# Duubel_v3.net
KiCad netlist of a schematic drawn in Altium Designer
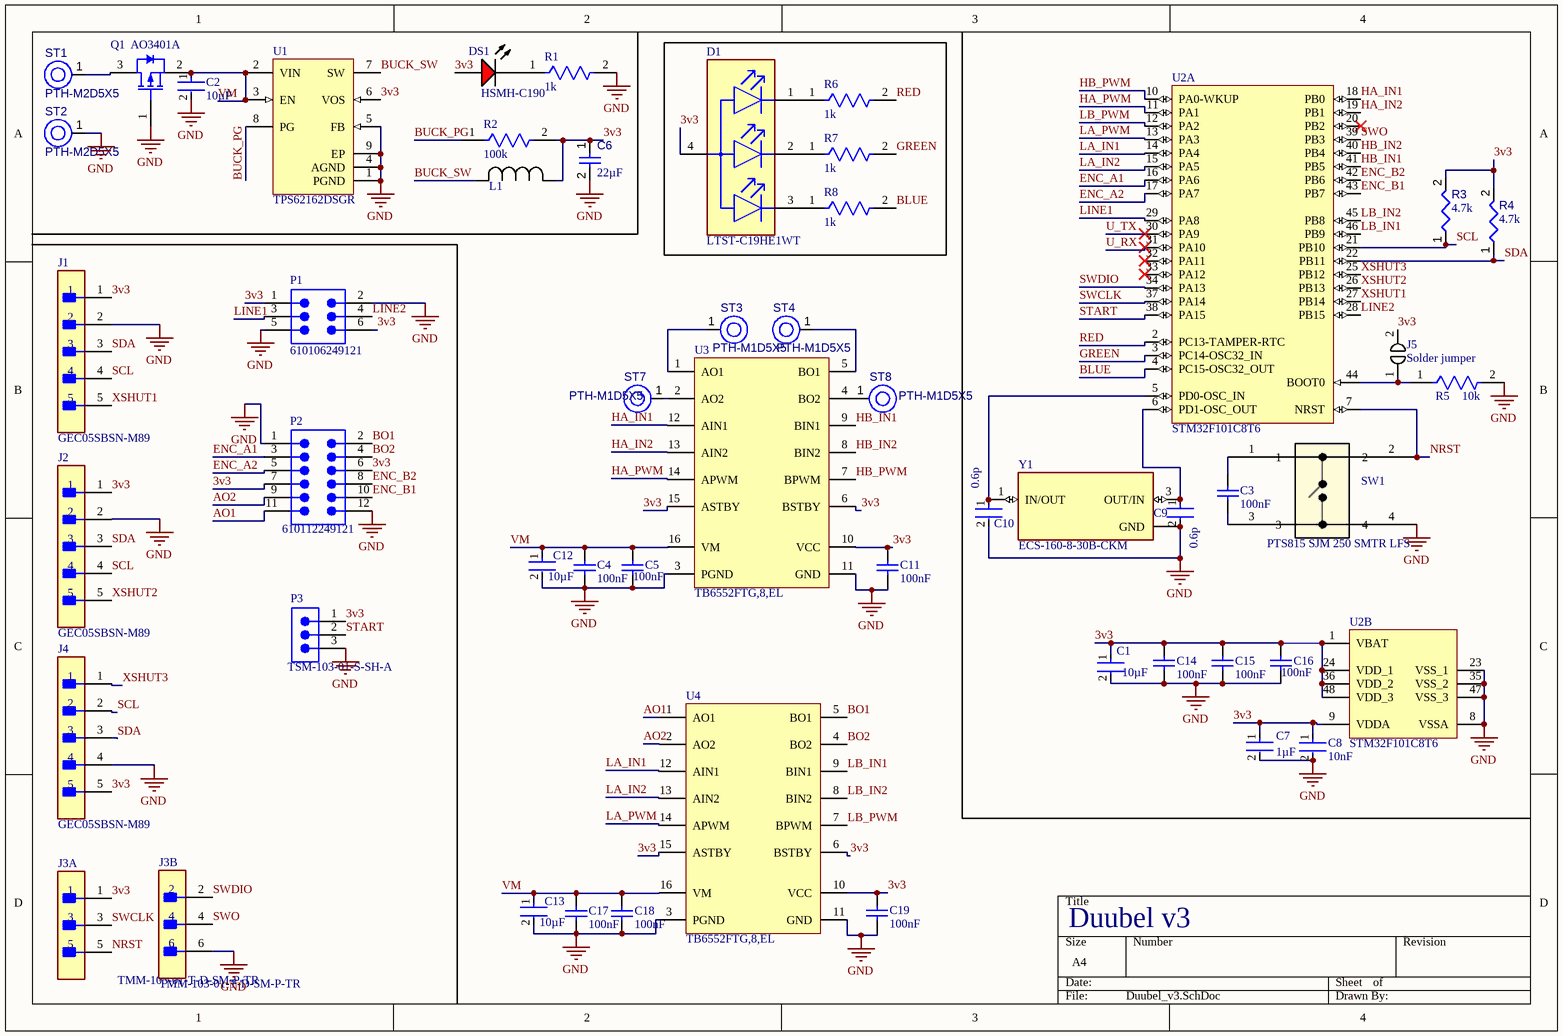
[diagram p0: Duubel_v3.SchDoc]

(export (version "E")
  (design (tool "Eeschema 10.0.6"))
  (components
    (comp (ref "C1")
      (value "10µF")
      (footprint "FP-CL10-IPC_B")
      (fields (field (name "Comment") "CL10A106KP8NNND"))
      (libsource (lib "TalTech") (part "b4654b650e69147ec39a6b967a45e02"))
    )
    (comp (ref "C2")
      (value "10µF")
      (footprint "FP-CL10-IPC_B")
      (fields (field (name "Comment") "CL10A106KP8NNND"))
      (libsource (lib "TalTech") (part "b4654b650e69147ec39a6b967a45e02"))
    )
    (comp (ref "C3")
      (value "100nF")
      (footprint "CAPC1608X90X35LL15T15")
      (fields (field (name "Comment") "0603YC104MAT4A"))
      (libsource (lib "TalTech") (part "CAP"))
    )
    (comp (ref "C4")
      (value "100nF")
      (footprint "CAPC1608X90X35LL15T15")
      (fields (field (name "Comment") "0603YC104MAT4A"))
      (libsource (lib "TalTech") (part "CAP"))
    )
    (comp (ref "C5")
      (value "100nF")
      (footprint "CAPC1608X90X35LL15T15")
      (fields (field (name "Comment") "0603YC104MAT4A"))
      (libsource (lib "TalTech") (part "CAP"))
    )
    (comp (ref "C6")
      (value "22µF")
      (footprint "CAPC0805(2012)145_L")
      (description "Chip Capacitor, 22µF +/-40%, 16V, 0805, Thickness 1.45 mm")
      (fields (field (name "TOLERANCE") "5%") (field (name "Comment") "Capacitor 22µF +/-40% 16V 0805"))
      (libsource (lib "TalTech") (part "CAP-NP-2"))
    )
    (comp (ref "C7")
      (value "1µF")
      (footprint "FP-0805-L_2_01_0_2-W_1_25-IPC_B")
      (fields (field (name "Comment") "08053C105K4Z2A"))
      (libsource (lib "TalTech") (part "b4654b650e69147ec39a6b967a45e02"))
    )
    (comp (ref "C8")
      (value "10nF")
      (footprint "FP-CL10-IPC_B")
      (fields (field (name "Comment") "CL10B103KB8NFNC"))
      (libsource (lib "TalTech") (part "b4654b650e69147ec39a6b967a45e02"))
    )
    (comp (ref "C9")
      (value "0.6p")
      (footprint "FP-CGA3E-0_3-0_1-MFG")
      (description "Cap Ceramic 6pF 50V C0G 0.5pF Pad SMD 0603 +125°C Automotive T/R")
      (libsource (lib "Altium Content Vault") (part "b4654b650e69147ec39a6b967a45e02"))
    )
    (comp (ref "C10")
      (value "0.6p")
      (footprint "FP-CGA3E-0_3-0_1-MFG")
      (description "Cap Ceramic 6pF 50V C0G 0.5pF Pad SMD 0603 +125°C Automotive T/R")
      (libsource (lib "Altium Content Vault") (part "b4654b650e69147ec39a6b967a45e02"))
    )
    (comp (ref "C11")
      (value "100nF")
      (footprint "CAPC1608X90X35LL15T15")
      (fields (field (name "Comment") "0603YC104MAT4A"))
      (libsource (lib "TalTech") (part "CAP"))
    )
    (comp (ref "C12")
      (value "10µF")
      (footprint "FP-CL10-IPC_B")
      (fields (field (name "Comment") "CL10A106KP8NNND"))
      (libsource (lib "TalTech") (part "b4654b650e69147ec39a6b967a45e02"))
    )
    (comp (ref "C13")
      (value "10µF")
      (footprint "FP-CL10-IPC_B")
      (fields (field (name "Comment") "CL10A106KP8NNND"))
      (libsource (lib "TalTech") (part "b4654b650e69147ec39a6b967a45e02"))
    )
    (comp (ref "C14")
      (value "100nF")
      (footprint "CAPC1608X90X35LL15T15")
      (fields (field (name "Comment") "0603YC104MAT4A"))
      (libsource (lib "TalTech") (part "CAP"))
    )
    (comp (ref "C15")
      (value "100nF")
      (footprint "CAPC1608X90X35LL15T15")
      (fields (field (name "Comment") "0603YC104MAT4A"))
      (libsource (lib "TalTech") (part "CAP"))
    )
    (comp (ref "C16")
      (value "100nF")
      (footprint "CAPC1608X90X35LL15T15")
      (fields (field (name "Comment") "0603YC104MAT4A"))
      (libsource (lib "TalTech") (part "CAP"))
    )
    (comp (ref "C17")
      (value "100nF")
      (footprint "CAPC1608X90X35LL15T15")
      (fields (field (name "Comment") "0603YC104MAT4A"))
      (libsource (lib "TalTech") (part "CAP"))
    )
    (comp (ref "C18")
      (value "100nF")
      (footprint "CAPC1608X90X35LL15T15")
      (fields (field (name "Comment") "0603YC104MAT4A"))
      (libsource (lib "TalTech") (part "CAP"))
    )
    (comp (ref "C19")
      (value "100nF")
      (footprint "CAPC1608X90X35LL15T15")
      (fields (field (name "Comment") "0603YC104MAT4A"))
      (libsource (lib "TalTech") (part "CAP"))
    )
    (comp (ref "D1")
      (value "LTST-C19HE1WT")
      (footprint "FP-LTST-C19HE1WT-MFG")
      (description "Single Color LED, White Diffused")
      (libsource (lib "TalTech") (part "2c4e1fdd461916b293eda504ca5a2b6"))
    )
    (comp (ref "DS1")
      (value "HSMH-C190")
      (footprint "AVAG-HSMX-C190_V")
      (description "LED Uni-Color Red, 65 mW, 20 mA, -40 to 85 degC, 2-Pin SMD, RoHS, Tape and Reel")
      (fields (field (name "POWER") "78mW") (field (name "MANUFACTURER") "Avago"))
      (libsource (lib "TalTech") (part "LED-RED-AK-2"))
    )
    (comp (ref "J1")
      (value "GEC05SBSN-M89")
      (footprint "FP-GEC05SBSN-M89-MFG")
      (description "Board Connector, 5 Contact(s), 1 Row(s), Male, Right Angle, Surface Mount Terminal")
      (libsource (lib "TalTech") (part "051ac7c1f60a91215dd69c4e70fad1a"))
    )
    (comp (ref "J2")
      (value "GEC05SBSN-M89")
      (footprint "FP-GEC05SBSN-M89-MFG")
      (description "Board Connector, 5 Contact(s), 1 Row(s), Male, Right Angle, Surface Mount Terminal")
      (libsource (lib "TalTech") (part "051ac7c1f60a91215dd69c4e70fad1a"))
    )
    (comp (ref "J3")
      (value "TMM-103-01-T-D-SM-P-TR")
      (footprint "FP-TMM-103-01-T-D-SM-P-TR-MFG")
      (libsource (lib "TalTech") (part "2654a11fb13586ecb194516b1c997bc"))
    )
    (comp (ref "J4")
      (value "GEC05SBSN-M89")
      (footprint "FP-GEC05SBSN-M89-MFG")
      (description "Board Connector, 5 Contact(s), 1 Row(s), Male, Right Angle, Surface Mount Terminal")
      (libsource (lib "TalTech") (part "051ac7c1f60a91215dd69c4e70fad1a"))
    )
    (comp (ref "J5")
      (value "Solder jumper")
      (footprint "Solder jumper-Footprint-1")
      (libsource (lib "TalTech") (part "New symbol 1"))
    )
    (comp (ref "L1")
      (value "IHHP0805ZHER2R2M01")
      (footprint "IND_IHHP-0805ZH-01_VIS")
      (description "Power Inductor, 2.2UH, Shielded, 1.8A Rohs Compliant: Yes")
      (libsource (lib "TalTech") (part "IHHP0805ZHER2R2M01"))
    )
    (comp (ref "P1")
      (value "610106249121")
      (footprint "610106249121")
      (description "Board Connector, 6 Contact(s), 2 Row(s), Male, Right Angle, Surface Mount Terminal")
      (libsource (lib "TalTech") (part "Header_Male_2R_06P"))
    )
    (comp (ref "P2")
      (value "610112249121")
      (footprint "610112249121")
      (description "Board Connector, 12 Contact(s), 2 Row(s), Male, Right Angle, Surface Mount Terminal")
      (libsource (lib "TalTech") (part "Header_Male_2R_12P"))
    )
    (comp (ref "P3")
      (value "TSM-103-01-S-SH-A")
      (footprint "SMTC-TSM-103-01-X-SH-A")
      (libsource (lib "TalTech") (part "SMTC-TSM-103-01-X-SH-A"))
    )
    (comp (ref "Q1")
      (value "AO3401A")
      (footprint "AO-SOT-23-3L_V")
      (libsource (lib "TalTech") (part "PEMOS-GSD-3"))
    )
    (comp (ref "R1")
      (value "1k")
      (footprint "FP-RCA0603-e3-IPC_B")
      (fields
        (field (name "TOLERANCE") "1%")
        (field (name "POWER") "100mW")
        (field (name "Comment") "RCA06031K00FKEA")
      )
      (libsource (lib "TalTech") (part "1029c3af85768c4190bb7ad29bc67b5"))
    )
    (comp (ref "R2")
      (value "100k")
      (footprint "FP-CRCW0603-HPe3-MFG")
      (fields
        (field (name "POWER") "250mW")
        (field (name "TOLERANCE") "5%")
        (field (name "Comment") "CRCW0603100KJNEAHP")
      )
      (libsource (lib "TalTech") (part "1029c3af85768c4190bb7ad29bc67b5"))
    )
    (comp (ref "R3")
      (value "4.7k")
      (footprint "RESC1608X55X25ML10T15")
      (description "Chip Resistor, 4.7 KOhm, +/- 1%, 0.1 W, -55 to 155 degC, 0603 (1608 Metric)")
      (fields (field (name "TOLERANCE") "1%") (field (name "POWER") "100mW"))
      (libsource (lib "TalTech") (part "RES-2"))
    )
    (comp (ref "R4")
      (value "4.7k")
      (footprint "RESC1608X55X25ML10T15")
      (description "Chip Resistor, 4.7 KOhm, +/- 1%, 0.1 W, -55 to 155 degC, 0603 (1608 Metric)")
      (fields (field (name "TOLERANCE") "1%") (field (name "POWER") "100mW"))
      (libsource (lib "TalTech") (part "RES-2"))
    )
    (comp (ref "R5")
      (value "10k")
      (footprint "FP-MCT0603-IPC_A")
      (description "Fixed Resistor, Thin Film, 0.1W, 10000ohm, 75V, 0.1% +/-Tol, 15ppm/Cel, Surface Mount, 0603")
      (fields (field (name "TOLERANCE") "0.1%") (field (name "POWER") "100mW"))
      (libsource (lib "TalTech") (part "1029c3af85768c4190bb7ad29bc67b5"))
    )
    (comp (ref "R6")
      (value "1k")
      (footprint "FP-RCA0603-e3-IPC_B")
      (fields
        (field (name "TOLERANCE") "1%")
        (field (name "POWER") "100mW")
        (field (name "Comment") "RCA06031K00FKEA")
      )
      (libsource (lib "TalTech") (part "1029c3af85768c4190bb7ad29bc67b5"))
    )
    (comp (ref "R7")
      (value "1k")
      (footprint "FP-RCA0603-e3-IPC_B")
      (fields
        (field (name "TOLERANCE") "1%")
        (field (name "POWER") "100mW")
        (field (name "Comment") "RCA06031K00FKEA")
      )
      (libsource (lib "TalTech") (part "1029c3af85768c4190bb7ad29bc67b5"))
    )
    (comp (ref "R8")
      (value "1k")
      (footprint "FP-RCA0603-e3-IPC_B")
      (fields
        (field (name "TOLERANCE") "1%")
        (field (name "POWER") "100mW")
        (field (name "Comment") "RCA06031K00FKEA")
      )
      (libsource (lib "TalTech") (part "1029c3af85768c4190bb7ad29bc67b5"))
    )
    (comp (ref "ST1")
      (value "PTH-M2D5X5")
      (footprint "PTH-M2D5X5")
      (description "M2 PTH (2.5mm), 5mm pad")
      (libsource (lib "TalTech") (part "CMP-00028-00000-1"))
    )
    (comp (ref "ST2")
      (value "PTH-M2D5X5")
      (footprint "PTH-M2D5X5")
      (description "M2 PTH (2.5mm), 5mm pad")
      (libsource (lib "TalTech") (part "CMP-00028-00000-1"))
    )
    (comp (ref "ST3")
      (value "PTH-M1D5X5")
      (footprint "PTH-M2D5X5")
      (description "M1 PTH (2.5mm), 5mm pad")
      (libsource (lib "TalTech") (part "CMP-00028-00000-1"))
    )
    (comp (ref "ST4")
      (value "PTH-M1D5X5")
      (footprint "PTH-M2D5X5")
      (description "M1 PTH (2.5mm), 5mm pad")
      (libsource (lib "TalTech") (part "CMP-00028-00000-1"))
    )
    (comp (ref "ST7")
      (value "PTH-M1D5X5")
      (footprint "PTH-M2D5X5")
      (description "M1 PTH (2.5mm), 5mm pad")
      (libsource (lib "TalTech") (part "CMP-00028-00000-1"))
    )
    (comp (ref "ST8")
      (value "PTH-M1D5X5")
      (footprint "PTH-M2D5X5")
      (description "M1 PTH (2.5mm), 5mm pad")
      (libsource (lib "TalTech") (part "CMP-00028-00000-1"))
    )
    (comp (ref "SW1")
      (value "PTS815 SJM 250 SMTR LFS")
      (footprint "SW4_PTS815 SJM 250 SMTR LFS_CNK")
      (description "No Description Available")
      (libsource (lib "PTS815SJM250SMTRLFS") (part "PTS815 SJM 250 SMTR LFS"))
    )
    (comp (ref "U1")
      (value "TPS62162DSGR")
      (footprint "DSG0008A_V")
      (description "Switching Regulator, Current-mode, 1A, 2250kHz Switching Freq-Max, PDSO8")
      (libsource (lib "TalTech") (part "TI-TPS62162DSG8-1600X900TP"))
    )
    (comp (ref "U2")
      (value "STM32F101C8T6")
      (footprint "STM-LQFP48_N")
      (description "RISC Microcontroller, 32-Bit, FLASH, CORTEX-M3 CPU, 36MHz, CMOS, PQFP48")
      (libsource (lib "TalTech") (part "MC-ARM-STM32F101X8_B-SQ48"))
    )
    (comp (ref "U3")
      (value "TB6552FTG,8,EL")
      (footprint "QFN50P300X300X75_HS-17N")
      (description "Dual-bridge Driver IC For DC Motors")
      (libsource (lib "TalTech") (part "TB6552FTG,8,EL-Symbol-1"))
    )
    (comp (ref "U4")
      (value "TB6552FTG,8,EL")
      (footprint "QFN50P300X300X75_HS-17N")
      (description "Dual-bridge Driver IC For DC Motors")
      (libsource (lib "TalTech") (part "TB6552FTG,8,EL-Symbol-1"))
    )
    (comp (ref "Y1")
      (value "ECS-160-8-30B-CKM")
      (footprint "XTAL_ECS-160-8-30B-CKM")
      (fields (field (name "MF") "{'manufacturer': u'ECS Inc.'}"))
      (libsource (lib "ECS-160-8-30B-CKM") (part "ECS-160-8-30B-CKM"))
    )
  )
  (nets
    (net (code "1") (name "/3v3") (class "Default")
      (node (ref "C1") (pin "1") (pinfunction "1_1") (pintype "passive"))
      (node (ref "C11") (pin "2") (pinfunction "2_2") (pintype "passive"))
      (node (ref "C14") (pin "2") (pinfunction "2_2") (pintype "passive"))
      (node (ref "C15") (pin "2") (pinfunction "2_2") (pintype "passive"))
      (node (ref "C16") (pin "2") (pinfunction "2_2") (pintype "passive"))
      (node (ref "C19") (pin "2") (pinfunction "2_2") (pintype "passive"))
      (node (ref "C6") (pin "1") (pinfunction "1_1") (pintype "passive"))
      (node (ref "C7") (pin "1") (pinfunction "1_1") (pintype "passive"))
      (node (ref "C8") (pin "1") (pinfunction "1_1") (pintype "passive"))
      (node (ref "D1") (pin "4") (pinfunction "A_4") (pintype "passive"))
      (node (ref "DS1") (pin "1") (pinfunction "A_1") (pintype "passive"))
      (node (ref "J1") (pin "1") (pinfunction "1_1") (pintype "passive"))
      (node (ref "J2") (pin "1") (pinfunction "1_1") (pintype "passive"))
      (node (ref "J3") (pin "1") (pinfunction "1_1") (pintype "passive"))
      (node (ref "J4") (pin "5") (pinfunction "5_5") (pintype "passive"))
      (node (ref "J5") (pin "2") (pintype "passive"))
      (node (ref "L1") (pin "1") (pinfunction "1_1") (pintype "passive"))
      (node (ref "P1") (pin "1") (pinfunction "1_1") (pintype "passive"))
      (node (ref "P1") (pin "6") (pinfunction "6_6") (pintype "passive"))
      (node (ref "P2") (pin "6") (pinfunction "6_6") (pintype "passive"))
      (node (ref "P2") (pin "7") (pinfunction "7_7") (pintype "passive"))
      (node (ref "P3") (pin "1") (pinfunction "1_1") (pintype "passive"))
      (node (ref "R2") (pin "2") (pinfunction "2_2") (pintype "passive"))
      (node (ref "R3") (pin "2") (pinfunction "2_2") (pintype "passive"))
      (node (ref "R4") (pin "2") (pinfunction "2_2") (pintype "passive"))
      (node (ref "U1") (pin "6") (pinfunction "VOS_6") (pintype "input"))
      (node (ref "U2") (pin "1") (pinfunction "VBAT_1") (pintype "power_in"))
      (node (ref "U2") (pin "24") (pinfunction "VDD_1_24") (pintype "power_in"))
      (node (ref "U2") (pin "36") (pinfunction "VDD_2_36") (pintype "power_in"))
      (node (ref "U2") (pin "48") (pinfunction "VDD_3_48") (pintype "power_in"))
      (node (ref "U2") (pin "9") (pinfunction "VDDA_9") (pintype "power_in"))
      (node (ref "U3") (pin "10") (pinfunction "VCC_10") (pintype "passive"))
      (node (ref "U3") (pin "15") (pinfunction "ASTBY_15") (pintype "passive"))
      (node (ref "U3") (pin "6") (pinfunction "BSTBY_6") (pintype "passive"))
      (node (ref "U4") (pin "10") (pinfunction "VCC_10") (pintype "passive"))
      (node (ref "U4") (pin "15") (pinfunction "ASTBY_15") (pintype "passive"))
      (node (ref "U4") (pin "6") (pinfunction "BSTBY_6") (pintype "passive"))
    )
    (net (code "2") (name "/AO1") (class "Default")
      (node (ref "P2") (pin "11") (pinfunction "11_11") (pintype "passive"))
      (node (ref "U4") (pin "1") (pinfunction "AO1_1") (pintype "passive"))
    )
    (net (code "3") (name "/AO2") (class "Default")
      (node (ref "P2") (pin "9") (pinfunction "9_9") (pintype "passive"))
      (node (ref "U4") (pin "2") (pinfunction "AO2_2") (pintype "passive"))
    )
    (net (code "4") (name "/BLUE") (class "Default")
      (node (ref "R8") (pin "2") (pinfunction "2_2") (pintype "passive"))
      (node (ref "U2") (pin "4") (pinfunction "PC15-OSC32_OUT_4") (pintype "bidirectional"))
    )
    (net (code "5") (name "/BO1") (class "Default")
      (node (ref "P2") (pin "2") (pinfunction "2_2") (pintype "passive"))
      (node (ref "U4") (pin "5") (pinfunction "BO1_5") (pintype "passive"))
    )
    (net (code "6") (name "/BO2") (class "Default")
      (node (ref "P2") (pin "4") (pinfunction "4_4") (pintype "passive"))
      (node (ref "U4") (pin "4") (pinfunction "BO2_4") (pintype "passive"))
    )
    (net (code "7") (name "/BUCK_PG") (class "Default")
      (node (ref "R2") (pin "1") (pinfunction "1_1") (pintype "passive"))
      (node (ref "U1") (pin "8") (pinfunction "PG_8") (pintype "tri_state"))
    )
    (net (code "8") (name "/BUCK_SW") (class "Default")
      (node (ref "L1") (pin "2") (pinfunction "2_2") (pintype "passive"))
      (node (ref "U1") (pin "7") (pinfunction "SW_7") (pintype "power_in"))
    )
    (net (code "9") (name "/ENC_A1") (class "Default")
      (node (ref "P2") (pin "3") (pinfunction "3_3") (pintype "passive"))
      (node (ref "U2") (pin "16") (pinfunction "PA6_16") (pintype "bidirectional"))
    )
    (net (code "10") (name "/ENC_A2") (class "Default")
      (node (ref "P2") (pin "5") (pinfunction "5_5") (pintype "passive"))
      (node (ref "U2") (pin "17") (pinfunction "PA7_17") (pintype "bidirectional"))
    )
    (net (code "11") (name "/ENC_B1") (class "Default")
      (node (ref "P2") (pin "10") (pinfunction "10_10") (pintype "passive"))
      (node (ref "U2") (pin "43") (pinfunction "PB7_43") (pintype "bidirectional"))
    )
    (net (code "12") (name "/ENC_B2") (class "Default")
      (node (ref "P2") (pin "8") (pinfunction "8_8") (pintype "passive"))
      (node (ref "U2") (pin "42") (pinfunction "PB6_42") (pintype "bidirectional"))
    )
    (net (code "13") (name "/GREEN") (class "Default")
      (node (ref "R7") (pin "2") (pinfunction "2_2") (pintype "passive"))
      (node (ref "U2") (pin "3") (pinfunction "PC14-OSC32_IN_3") (pintype "bidirectional"))
    )
    (net (code "14") (name "/HA_IN1") (class "Default")
      (node (ref "U2") (pin "18") (pinfunction "PB0_18") (pintype "bidirectional"))
      (node (ref "U3") (pin "12") (pinfunction "AIN1_12") (pintype "passive"))
    )
    (net (code "15") (name "/HA_IN2") (class "Default")
      (node (ref "U2") (pin "19") (pinfunction "PB1_19") (pintype "bidirectional"))
      (node (ref "U3") (pin "13") (pinfunction "AIN2_13") (pintype "passive"))
    )
    (net (code "16") (name "/HA_PWM") (class "Default")
      (node (ref "U2") (pin "11") (pinfunction "PA1_11") (pintype "bidirectional"))
      (node (ref "U3") (pin "14") (pinfunction "APWM_14") (pintype "passive"))
    )
    (net (code "17") (name "/HB_IN1") (class "Default")
      (node (ref "U2") (pin "41") (pinfunction "PB5_41") (pintype "bidirectional"))
      (node (ref "U3") (pin "9") (pinfunction "BIN1_9") (pintype "passive"))
    )
    (net (code "18") (name "/HB_IN2") (class "Default")
      (node (ref "U2") (pin "40") (pinfunction "PB4_40") (pintype "bidirectional"))
      (node (ref "U3") (pin "8") (pinfunction "BIN2_8") (pintype "passive"))
    )
    (net (code "19") (name "/HB_PWM") (class "Default")
      (node (ref "U2") (pin "10") (pinfunction "PA0-WKUP_10") (pintype "bidirectional"))
      (node (ref "U3") (pin "7") (pinfunction "BPWM_7") (pintype "passive"))
    )
    (net (code "20") (name "/LA_IN1") (class "Default")
      (node (ref "U2") (pin "14") (pinfunction "PA4_14") (pintype "bidirectional"))
      (node (ref "U4") (pin "12") (pinfunction "AIN1_12") (pintype "passive"))
    )
    (net (code "21") (name "/LA_IN2") (class "Default")
      (node (ref "U2") (pin "15") (pinfunction "PA5_15") (pintype "bidirectional"))
      (node (ref "U4") (pin "13") (pinfunction "AIN2_13") (pintype "passive"))
    )
    (net (code "22") (name "/LA_PWM") (class "Default")
      (node (ref "U2") (pin "13") (pinfunction "PA3_13") (pintype "bidirectional"))
      (node (ref "U4") (pin "14") (pinfunction "APWM_14") (pintype "passive"))
    )
    (net (code "23") (name "/LB_IN1") (class "Default")
      (node (ref "U2") (pin "46") (pinfunction "PB9_46") (pintype "bidirectional"))
      (node (ref "U4") (pin "9") (pinfunction "BIN1_9") (pintype "passive"))
    )
    (net (code "24") (name "/LB_IN2") (class "Default")
      (node (ref "U2") (pin "45") (pinfunction "PB8_45") (pintype "bidirectional"))
      (node (ref "U4") (pin "8") (pinfunction "BIN2_8") (pintype "passive"))
    )
    (net (code "25") (name "/LB_PWM") (class "Default")
      (node (ref "U2") (pin "12") (pinfunction "PA2_12") (pintype "bidirectional"))
      (node (ref "U4") (pin "7") (pinfunction "BPWM_7") (pintype "passive"))
    )
    (net (code "26") (name "/LINE1") (class "Default")
      (node (ref "P1") (pin "3") (pinfunction "3_3") (pintype "passive"))
      (node (ref "U2") (pin "29") (pinfunction "PA8_29") (pintype "bidirectional"))
    )
    (net (code "27") (name "/LINE2") (class "Default")
      (node (ref "P1") (pin "4") (pinfunction "4_4") (pintype "passive"))
      (node (ref "U2") (pin "28") (pinfunction "PB15_28") (pintype "bidirectional"))
    )
    (net (code "28") (name "/NRST") (class "Default")
      (node (ref "J3") (pin "5") (pinfunction "5_5") (pintype "passive"))
      (node (ref "SW1") (pin "2") (pinfunction "2_2") (pintype "passive"))
      (node (ref "U2") (pin "7") (pinfunction "NRST_7") (pintype "bidirectional"))
    )
    (net (code "29") (name "/RED") (class "Default")
      (node (ref "R6") (pin "2") (pinfunction "2_2") (pintype "passive"))
      (node (ref "U2") (pin "2") (pinfunction "PC13-TAMPER-RTC_2") (pintype "bidirectional"))
    )
    (net (code "30") (name "/SCL") (class "Default")
      (node (ref "J1") (pin "4") (pinfunction "4_4") (pintype "passive"))
      (node (ref "J2") (pin "4") (pinfunction "4_4") (pintype "passive"))
      (node (ref "J4") (pin "2") (pinfunction "2_2") (pintype "passive"))
      (node (ref "R3") (pin "1") (pinfunction "1_1") (pintype "passive"))
      (node (ref "U2") (pin "21") (pinfunction "PB10_21") (pintype "bidirectional"))
    )
    (net (code "31") (name "/SDA") (class "Default")
      (node (ref "J1") (pin "3") (pinfunction "3_3") (pintype "passive"))
      (node (ref "J2") (pin "3") (pinfunction "3_3") (pintype "passive"))
      (node (ref "J4") (pin "3") (pinfunction "3_3") (pintype "passive"))
      (node (ref "R4") (pin "1") (pinfunction "1_1") (pintype "passive"))
      (node (ref "U2") (pin "22") (pinfunction "PB11_22") (pintype "bidirectional"))
    )
    (net (code "32") (name "/START") (class "Default")
      (node (ref "P3") (pin "2") (pinfunction "2_2") (pintype "passive"))
      (node (ref "U2") (pin "38") (pinfunction "PA15_38") (pintype "bidirectional"))
    )
    (net (code "33") (name "/SWCLK") (class "Default")
      (node (ref "J3") (pin "3") (pinfunction "3_3") (pintype "passive"))
      (node (ref "U2") (pin "37") (pinfunction "PA14_37") (pintype "bidirectional"))
    )
    (net (code "34") (name "/SWDIO") (class "Default")
      (node (ref "J3") (pin "2") (pinfunction "2_2") (pintype "passive"))
      (node (ref "U2") (pin "34") (pinfunction "PA13_34") (pintype "bidirectional"))
    )
    (net (code "35") (name "/SWO") (class "Default")
      (node (ref "J3") (pin "4") (pinfunction "4_4") (pintype "passive"))
      (node (ref "U2") (pin "39") (pinfunction "PB3_39") (pintype "bidirectional"))
    )
    (net (code "36") (name "/U_RX") (class "Default")
      (node (ref "U2") (pin "31") (pinfunction "PA10_31") (pintype "bidirectional+no_connect"))
    )
    (net (code "37") (name "/U_TX") (class "Default")
      (node (ref "U2") (pin "30") (pinfunction "PA9_30") (pintype "bidirectional+no_connect"))
    )
    (net (code "38") (name "/VM") (class "Default")
      (node (ref "C12") (pin "1") (pinfunction "1_1") (pintype "passive"))
      (node (ref "C13") (pin "1") (pinfunction "1_1") (pintype "passive"))
      (node (ref "C17") (pin "2") (pinfunction "2_2") (pintype "passive"))
      (node (ref "C18") (pin "2") (pinfunction "2_2") (pintype "passive"))
      (node (ref "C2") (pin "1") (pinfunction "1_1") (pintype "passive"))
      (node (ref "C4") (pin "2") (pinfunction "2_2") (pintype "passive"))
      (node (ref "C5") (pin "2") (pinfunction "2_2") (pintype "passive"))
      (node (ref "Q1") (pin "2") (pinfunction "SOURCE_2") (pintype "passive"))
      (node (ref "U1") (pin "2") (pinfunction "VIN_2") (pintype "power_in"))
      (node (ref "U1") (pin "3") (pinfunction "EN_3") (pintype "input"))
      (node (ref "U3") (pin "16") (pinfunction "VM_16") (pintype "passive"))
      (node (ref "U4") (pin "16") (pinfunction "VM_16") (pintype "passive"))
    )
    (net (code "39") (name "/XSHUT1") (class "Default")
      (node (ref "J1") (pin "5") (pinfunction "5_5") (pintype "passive"))
      (node (ref "U2") (pin "27") (pinfunction "PB14_27") (pintype "bidirectional"))
    )
    (net (code "40") (name "/XSHUT2") (class "Default")
      (node (ref "J2") (pin "5") (pinfunction "5_5") (pintype "passive"))
      (node (ref "U2") (pin "26") (pinfunction "PB13_26") (pintype "bidirectional"))
    )
    (net (code "41") (name "/XSHUT3") (class "Default")
      (node (ref "J4") (pin "1") (pinfunction "1_1") (pintype "passive"))
      (node (ref "U2") (pin "25") (pinfunction "PB12_25") (pintype "bidirectional"))
    )
    (net (code "42") (name "GND") (class "Default")
      (node (ref "C1") (pin "2") (pinfunction "2_2") (pintype "passive"))
      (node (ref "C10") (pin "2") (pinfunction "2_2") (pintype "passive"))
      (node (ref "C11") (pin "1") (pinfunction "1_1") (pintype "passive"))
      (node (ref "C12") (pin "2") (pinfunction "2_2") (pintype "passive"))
      (node (ref "C13") (pin "2") (pinfunction "2_2") (pintype "passive"))
      (node (ref "C14") (pin "1") (pinfunction "1_1") (pintype "passive"))
      (node (ref "C15") (pin "1") (pinfunction "1_1") (pintype "passive"))
      (node (ref "C16") (pin "1") (pinfunction "1_1") (pintype "passive"))
      (node (ref "C17") (pin "1") (pinfunction "1_1") (pintype "passive"))
      (node (ref "C18") (pin "1") (pinfunction "1_1") (pintype "passive"))
      (node (ref "C19") (pin "1") (pinfunction "1_1") (pintype "passive"))
      (node (ref "C2") (pin "2") (pinfunction "2_2") (pintype "passive"))
      (node (ref "C4") (pin "1") (pinfunction "1_1") (pintype "passive"))
      (node (ref "C5") (pin "1") (pinfunction "1_1") (pintype "passive"))
      (node (ref "C6") (pin "2") (pinfunction "2_2") (pintype "passive"))
      (node (ref "C7") (pin "2") (pinfunction "2_2") (pintype "passive"))
      (node (ref "C8") (pin "2") (pinfunction "2_2") (pintype "passive"))
      (node (ref "C9") (pin "2") (pinfunction "2_2") (pintype "passive"))
      (node (ref "J1") (pin "2") (pinfunction "2_2") (pintype "passive"))
      (node (ref "J2") (pin "2") (pinfunction "2_2") (pintype "passive"))
      (node (ref "J3") (pin "6") (pinfunction "6_6") (pintype "passive"))
      (node (ref "J4") (pin "4") (pinfunction "4_4") (pintype "passive"))
      (node (ref "P1") (pin "2") (pinfunction "2_2") (pintype "passive"))
      (node (ref "P1") (pin "5") (pinfunction "5_5") (pintype "passive"))
      (node (ref "P2") (pin "1") (pinfunction "1_1") (pintype "passive"))
      (node (ref "P2") (pin "12") (pinfunction "12_12") (pintype "passive"))
      (node (ref "P3") (pin "3") (pinfunction "3_3") (pintype "passive"))
      (node (ref "Q1") (pin "1") (pinfunction "GATE_1") (pintype "passive"))
      (node (ref "R1") (pin "2") (pinfunction "2_2") (pintype "passive"))
      (node (ref "R5") (pin "2") (pinfunction "2_2") (pintype "passive"))
      (node (ref "ST2") (pin "1") (pinfunction "H1_1") (pintype "passive"))
      (node (ref "SW1") (pin "4") (pinfunction "4_4") (pintype "passive"))
      (node (ref "U1") (pin "1") (pinfunction "PGND_1") (pintype "power_in"))
      (node (ref "U1") (pin "4") (pinfunction "AGND_4") (pintype "power_in"))
      (node (ref "U1") (pin "5") (pinfunction "FB_5") (pintype "input"))
      (node (ref "U1") (pin "9") (pinfunction "EP_9") (pintype "power_in"))
      (node (ref "U2") (pin "23") (pinfunction "VSS_1_23") (pintype "power_in"))
      (node (ref "U2") (pin "35") (pinfunction "VSS_2_35") (pintype "power_in"))
      (node (ref "U2") (pin "47") (pinfunction "VSS_3_47") (pintype "power_in"))
      (node (ref "U2") (pin "8") (pinfunction "VSSA_8") (pintype "power_in"))
      (node (ref "U3") (pin "11") (pinfunction "GND_11") (pintype "passive"))
      (node (ref "U3") (pin "3") (pinfunction "PGND_3") (pintype "passive"))
      (node (ref "U4") (pin "11") (pinfunction "GND_11") (pintype "passive"))
      (node (ref "U4") (pin "3") (pinfunction "PGND_3") (pintype "passive"))
      (node (ref "Y1") (pin "2") (pinfunction "GND_2") (pintype "power_in"))
      (node (ref "Y1") (pin "4") (pinfunction "GND_4") (pintype "power_in"))
    )
    (net (code "43") (name "Net-(C3-Pad1)") (class "Default")
      (node (ref "C3") (pin "1") (pinfunction "1_1") (pintype "passive"))
      (node (ref "SW1") (pin "3") (pinfunction "3_3") (pintype "passive"))
    )
    (net (code "44") (name "Net-(C3-Pad2)") (class "Default")
      (node (ref "C3") (pin "2") (pinfunction "2_2") (pintype "passive"))
      (node (ref "SW1") (pin "1") (pinfunction "1_1") (pintype "passive"))
    )
    (net (code "45") (name "Net-(D1-BLUE_C)") (class "Default")
      (node (ref "D1") (pin "3") (pinfunction "BLUE_C_3") (pintype "passive"))
      (node (ref "R8") (pin "1") (pinfunction "1_1") (pintype "passive"))
    )
    (net (code "46") (name "Net-(D1-GREEN_C)") (class "Default")
      (node (ref "D1") (pin "2") (pinfunction "GREEN_C_2") (pintype "passive"))
      (node (ref "R7") (pin "1") (pinfunction "1_1") (pintype "passive"))
    )
    (net (code "47") (name "Net-(D1-RED_C)") (class "Default")
      (node (ref "D1") (pin "1") (pinfunction "RED_C_1") (pintype "passive"))
      (node (ref "R6") (pin "1") (pinfunction "1_1") (pintype "passive"))
    )
    (net (code "48") (name "Net-(DS1-K)") (class "Default")
      (node (ref "DS1") (pin "2") (pinfunction "K_2") (pintype "passive"))
      (node (ref "R1") (pin "1") (pinfunction "1_1") (pintype "passive"))
    )
    (net (code "49") (name "Net-(Q1-DRAIN)") (class "Default")
      (node (ref "Q1") (pin "3") (pinfunction "DRAIN_3") (pintype "passive"))
      (node (ref "ST1") (pin "1") (pinfunction "H1_1") (pintype "passive"))
    )
    (net (code "50") (name "Net-(ST3-H1)") (class "Default")
      (node (ref "ST3") (pin "1") (pinfunction "H1_1") (pintype "passive"))
      (node (ref "U3") (pin "1") (pinfunction "AO1_1") (pintype "passive"))
    )
    (net (code "51") (name "Net-(ST4-H1)") (class "Default")
      (node (ref "ST4") (pin "1") (pinfunction "H1_1") (pintype "passive"))
      (node (ref "U3") (pin "5") (pinfunction "BO1_5") (pintype "passive"))
    )
    (net (code "52") (name "Net-(ST7-H1)") (class "Default")
      (node (ref "ST7") (pin "1") (pinfunction "H1_1") (pintype "passive"))
      (node (ref "U3") (pin "2") (pinfunction "AO2_2") (pintype "passive"))
    )
    (net (code "53") (name "Net-(ST8-H1)") (class "Default")
      (node (ref "ST8") (pin "1") (pinfunction "H1_1") (pintype "passive"))
      (node (ref "U3") (pin "4") (pinfunction "BO2_4") (pintype "passive"))
    )
    (net (code "54") (name "Net-(U2A-BOOT0)") (class "Default")
      (node (ref "J5") (pin "1") (pintype "passive"))
      (node (ref "R5") (pin "1") (pinfunction "1_1") (pintype "passive"))
      (node (ref "U2") (pin "44") (pinfunction "BOOT0_44") (pintype "input"))
    )
    (net (code "55") (name "Net-(U2A-PD0-OSC_IN)") (class "Default")
      (node (ref "C10") (pin "1") (pinfunction "1_1") (pintype "passive"))
      (node (ref "U2") (pin "5") (pinfunction "PD0-OSC_IN_5") (pintype "bidirectional"))
      (node (ref "Y1") (pin "1") (pinfunction "IN/OUT_1") (pintype "bidirectional"))
    )
    (net (code "56") (name "Net-(U2A-PD1-OSC_OUT)") (class "Default")
      (node (ref "C9") (pin "1") (pinfunction "1_1") (pintype "passive"))
      (node (ref "U2") (pin "6") (pinfunction "PD1-OSC_OUT_6") (pintype "bidirectional"))
      (node (ref "Y1") (pin "3") (pinfunction "OUT/IN_3") (pintype "bidirectional"))
    )
    (net (code "57") (name "unconnected-(U2A-PA11-Pad32)") (class "Default")
      (node (ref "U2") (pin "32") (pinfunction "PA11_32") (pintype "bidirectional+no_connect"))
    )
    (net (code "58") (name "unconnected-(U2A-PA12-Pad33)") (class "Default")
      (node (ref "U2") (pin "33") (pinfunction "PA12_33") (pintype "bidirectional+no_connect"))
    )
    (net (code "59") (name "unconnected-(U2A-PB2-Pad20)") (class "Default")
      (node (ref "U2") (pin "20") (pinfunction "PB2_20") (pintype "bidirectional+no_connect"))
    )
  )
)
